# expansion_module_USB_host.net
KiCad netlist of a schematic drawn in EAGLE
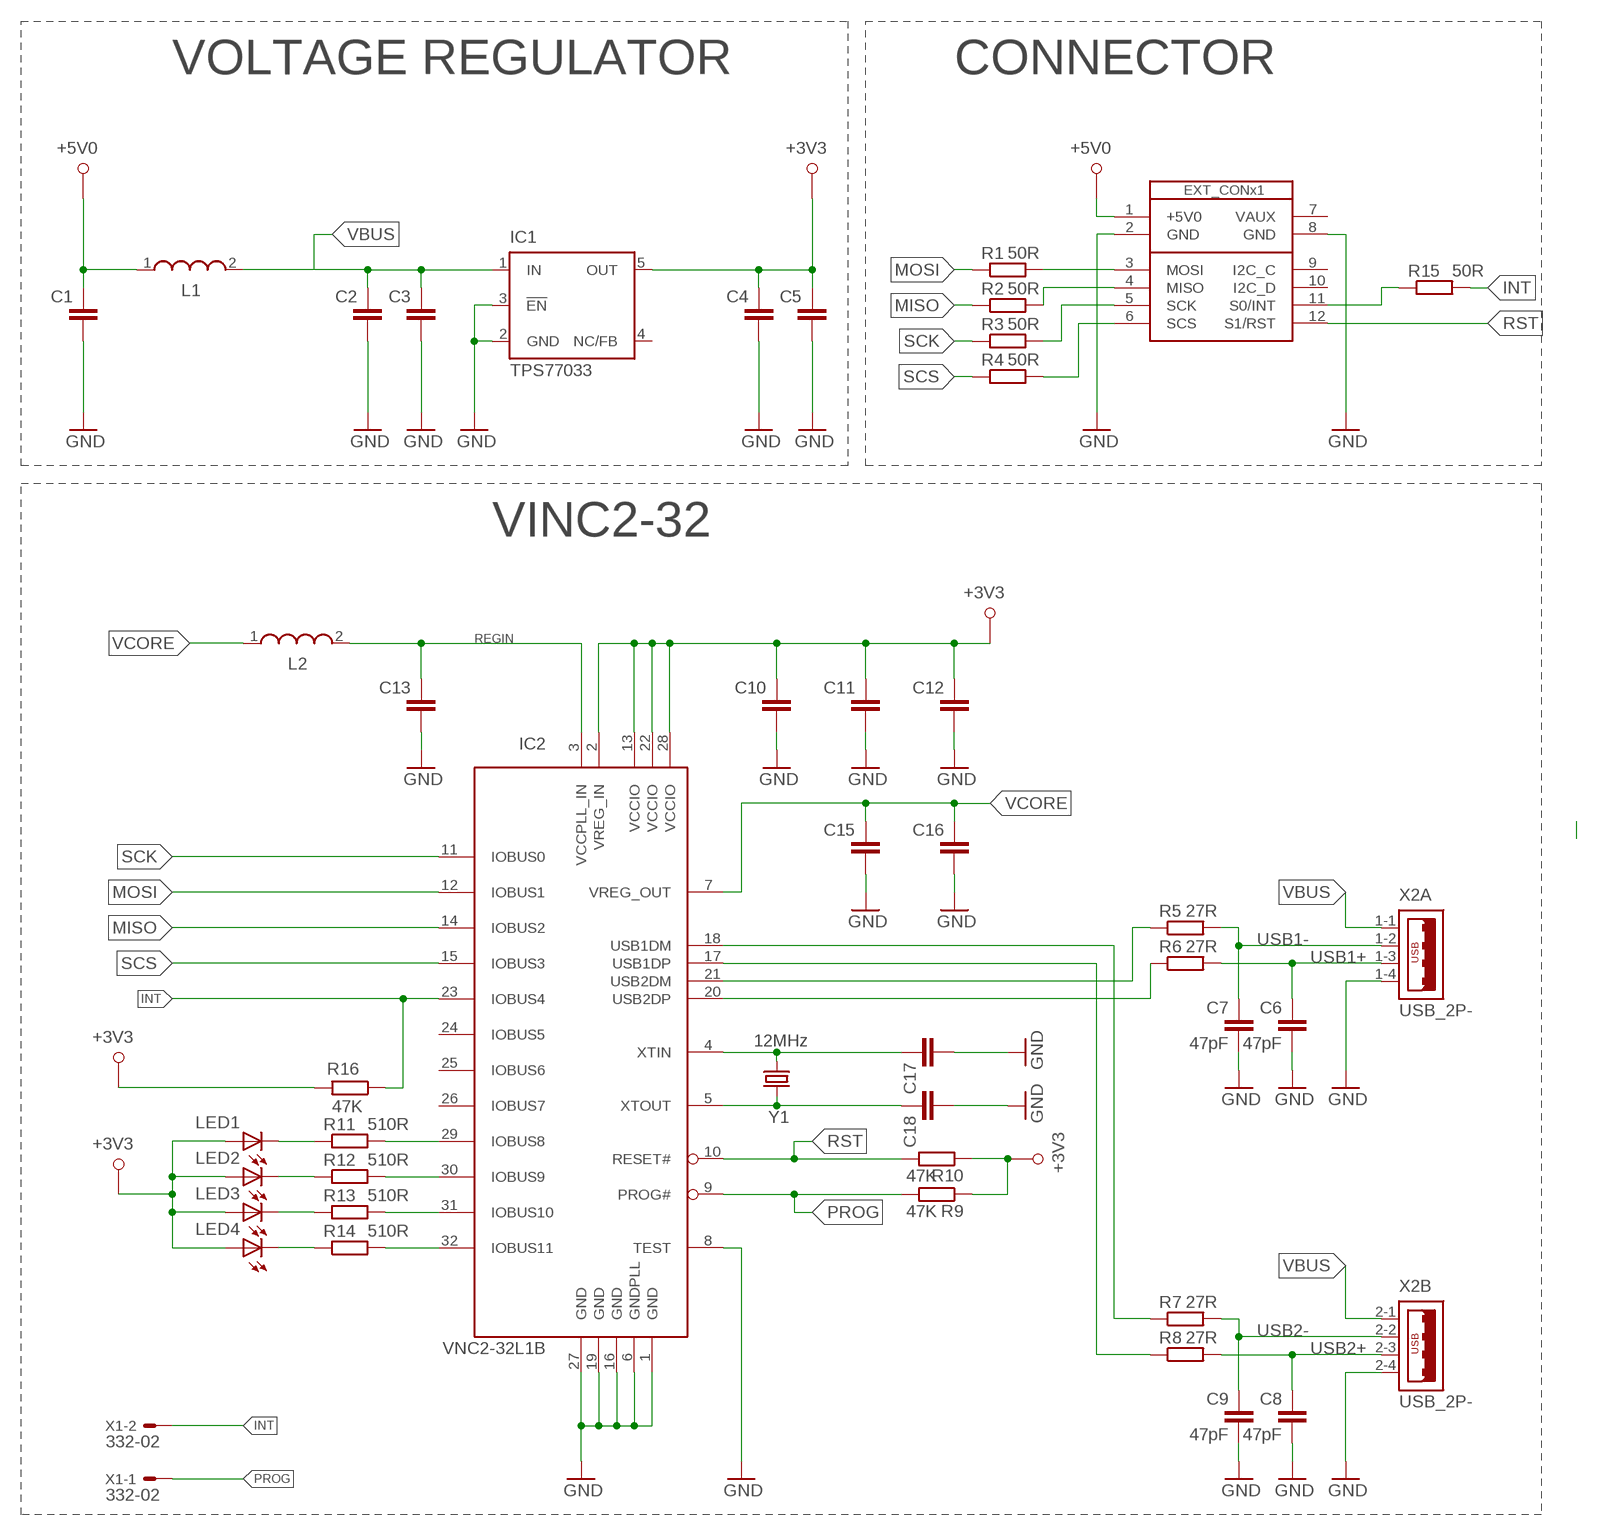
[diagram p0: schematic, sheet 1]

(export (version "E")
  (design (tool "Eeschema 10.0.6"))
  (components
    (comp (ref "C1")
      (value "C-EUC0805")
      (footprint "eagle-import:C0805")
      (libsource (lib "eagle-import") (part "C-EUC0805"))
    )
    (comp (ref "C2")
      (value "C-EUC0805")
      (footprint "eagle-import:C0805")
      (libsource (lib "eagle-import") (part "C-EUC0805"))
    )
    (comp (ref "C3")
      (value "C-EUC0805")
      (footprint "eagle-import:C0805")
      (libsource (lib "eagle-import") (part "C-EUC0805"))
    )
    (comp (ref "C4")
      (value "C-EUC0805")
      (footprint "eagle-import:C0805")
      (libsource (lib "eagle-import") (part "C-EUC0805"))
    )
    (comp (ref "C5")
      (value "C-EUC0805")
      (footprint "eagle-import:C0805")
      (libsource (lib "eagle-import") (part "C-EUC0805"))
    )
    (comp (ref "C6")
      (value "47pF")
      (footprint "eagle-import:C0805")
      (libsource (lib "eagle-import") (part "C-EUC0805"))
    )
    (comp (ref "C7")
      (value "47pF")
      (footprint "eagle-import:C0805")
      (libsource (lib "eagle-import") (part "C-EUC0805"))
    )
    (comp (ref "C8")
      (value "47pF")
      (footprint "eagle-import:C0805")
      (libsource (lib "eagle-import") (part "C-EUC0805"))
    )
    (comp (ref "C9")
      (value "47pF")
      (footprint "eagle-import:C0805")
      (libsource (lib "eagle-import") (part "C-EUC0805"))
    )
    (comp (ref "C10")
      (value "C-EUC0805")
      (footprint "eagle-import:C0805")
      (libsource (lib "eagle-import") (part "C-EUC0805"))
    )
    (comp (ref "C11")
      (value "C-EUC0805")
      (footprint "eagle-import:C0805")
      (libsource (lib "eagle-import") (part "C-EUC0805"))
    )
    (comp (ref "C12")
      (value "C-EUC0805")
      (footprint "eagle-import:C0805")
      (libsource (lib "eagle-import") (part "C-EUC0805"))
    )
    (comp (ref "C13")
      (value "C-EUC0805")
      (footprint "eagle-import:C0805")
      (libsource (lib "eagle-import") (part "C-EUC0805"))
    )
    (comp (ref "C15")
      (value "C-EUC0805")
      (footprint "eagle-import:C0805")
      (libsource (lib "eagle-import") (part "C-EUC0805"))
    )
    (comp (ref "C16")
      (value "C-EUC0805")
      (footprint "eagle-import:C0805")
      (libsource (lib "eagle-import") (part "C-EUC0805"))
    )
    (comp (ref "C17")
      (value "C-EUC0805")
      (footprint "eagle-import:C0805")
      (libsource (lib "eagle-import") (part "C-EUC0805"))
    )
    (comp (ref "C18")
      (value "C-EUC0805")
      (footprint "eagle-import:C0805")
      (libsource (lib "eagle-import") (part "C-EUC0805"))
    )
    (comp (ref "IC1")
      (value "TPS77033")
      (footprint "eagle-import:SOT23-DBV")
      (fields (field (name "MF") "TEXAS INSTRUMENTS") (field (name "MPN") "TPS77033DBVT"))
      (libsource (lib "eagle-import") (part "TPS77033"))
    )
    (comp (ref "IC2")
      (value "VNC2-32L1B")
      (footprint "eagle-import:LQFP32")
      (libsource (lib "eagle-import") (part "VNC2-32L1B"))
    )
    (comp (ref "L1")
      (value "WE-LQ_1210")
      (footprint "eagle-import:WE-LQ_M")
      (libsource (lib "eagle-import") (part "WE-LQ_1210"))
    )
    (comp (ref "L2")
      (value "WE-LQ_1210")
      (footprint "eagle-import:WE-LQ_M")
      (libsource (lib "eagle-import") (part "WE-LQ_1210"))
    )
    (comp (ref "LED1")
      (value "LEDCHIPLED_0805")
      (footprint "eagle-import:CHIPLED_0805")
      (libsource (lib "eagle-import") (part "LEDCHIPLED_0805"))
    )
    (comp (ref "LED2")
      (value "LEDCHIPLED_0805")
      (footprint "eagle-import:CHIPLED_0805")
      (libsource (lib "eagle-import") (part "LEDCHIPLED_0805"))
    )
    (comp (ref "LED3")
      (value "LEDCHIPLED_0805")
      (footprint "eagle-import:CHIPLED_0805")
      (libsource (lib "eagle-import") (part "LEDCHIPLED_0805"))
    )
    (comp (ref "LED4")
      (value "LEDCHIPLED_0805")
      (footprint "eagle-import:CHIPLED_0805")
      (libsource (lib "eagle-import") (part "LEDCHIPLED_0805"))
    )
    (comp (ref "R1")
      (value "50R")
      (footprint "eagle-import:R0805")
      (libsource (lib "eagle-import") (part "R-EU_R0805"))
    )
    (comp (ref "R2")
      (value "50R")
      (footprint "eagle-import:R0805")
      (libsource (lib "eagle-import") (part "R-EU_R0805"))
    )
    (comp (ref "R3")
      (value "50R")
      (footprint "eagle-import:R0805")
      (libsource (lib "eagle-import") (part "R-EU_R0805"))
    )
    (comp (ref "R4")
      (value "50R")
      (footprint "eagle-import:R0805")
      (libsource (lib "eagle-import") (part "R-EU_R0805"))
    )
    (comp (ref "R5")
      (value "27R")
      (footprint "eagle-import:R0805")
      (libsource (lib "eagle-import") (part "R-EU_R0805"))
    )
    (comp (ref "R6")
      (value "27R")
      (footprint "eagle-import:R0805")
      (libsource (lib "eagle-import") (part "R-EU_R0805"))
    )
    (comp (ref "R7")
      (value "27R")
      (footprint "eagle-import:R0805")
      (libsource (lib "eagle-import") (part "R-EU_R0805"))
    )
    (comp (ref "R8")
      (value "27R")
      (footprint "eagle-import:R0805")
      (libsource (lib "eagle-import") (part "R-EU_R0805"))
    )
    (comp (ref "R9")
      (value "47K")
      (footprint "eagle-import:R0805")
      (libsource (lib "eagle-import") (part "R-EU_R0805"))
    )
    (comp (ref "R10")
      (value "47K")
      (footprint "eagle-import:R0805")
      (libsource (lib "eagle-import") (part "R-EU_R0805"))
    )
    (comp (ref "R11")
      (value "510R")
      (footprint "eagle-import:R0805")
      (libsource (lib "eagle-import") (part "R-EU_R0805"))
    )
    (comp (ref "R12")
      (value "510R")
      (footprint "eagle-import:R0805")
      (libsource (lib "eagle-import") (part "R-EU_R0805"))
    )
    (comp (ref "R13")
      (value "510R")
      (footprint "eagle-import:R0805")
      (libsource (lib "eagle-import") (part "R-EU_R0805"))
    )
    (comp (ref "R14")
      (value "510R")
      (footprint "eagle-import:R0805")
      (libsource (lib "eagle-import") (part "R-EU_R0805"))
    )
    (comp (ref "R15")
      (value "50R")
      (footprint "eagle-import:R0805")
      (libsource (lib "eagle-import") (part "R-EU_R0805"))
    )
    (comp (ref "R16")
      (value "47K")
      (footprint "eagle-import:R0805")
      (libsource (lib "eagle-import") (part "R-EU_R0805"))
    )
    (comp (ref "U$1")
      (value "SB_EXT_CON_X1_SPI")
      (footprint "eagle-import:SB_EXT_CON_X1_FULL")
      (libsource (lib "eagle-import") (part "SB_EXT_CON_X1_SPI"))
    )
    (comp (ref "X1")
      (value "332-02")
      (footprint "eagle-import:332-02")
      (libsource (lib "eagle-import") (part "332-02"))
    )
    (comp (ref "X2")
      (value "USB_2P-")
      (footprint "eagle-import:85-32003-00X-1_DUAL")
      (libsource (lib "eagle-import") (part "USB_2P-"))
    )
    (comp (ref "Y1")
      (value "12MHz")
      (footprint "eagle-import:CRYSTAL-SMD-5X3")
      (libsource (lib "eagle-import") (part "CRYSTALCRYSTAL-SMD-5X3-12MHZ"))
    )
  )
  (nets
    (net (code "1") (name "+3V3") (class "Default")
      (node (ref "C10") (pin "2") (pinfunction "2_2") (pintype "passive"))
      (node (ref "C11") (pin "2") (pinfunction "2_2") (pintype "passive"))
      (node (ref "C12") (pin "2") (pinfunction "2_2") (pintype "passive"))
      (node (ref "C4") (pin "2") (pinfunction "2_2") (pintype "passive"))
      (node (ref "C5") (pin "2") (pinfunction "2_2") (pintype "passive"))
      (node (ref "IC1") (pin "5") (pinfunction "OUT_5") (pintype "passive"))
      (node (ref "IC2") (pin "13") (pinfunction "VCCIO_13") (pintype "power_in"))
      (node (ref "IC2") (pin "2") (pinfunction "VREG_IN_2") (pintype "power_in"))
      (node (ref "IC2") (pin "22") (pinfunction "VCCIO_22") (pintype "power_in"))
      (node (ref "IC2") (pin "28") (pinfunction "VCCIO_28") (pintype "power_in"))
      (node (ref "LED1") (pin "A") (pinfunction "A_A") (pintype "passive"))
      (node (ref "LED2") (pin "A") (pinfunction "A_A") (pintype "passive"))
      (node (ref "LED3") (pin "A") (pinfunction "A_A") (pintype "passive"))
      (node (ref "LED4") (pin "A") (pinfunction "A_A") (pintype "passive"))
      (node (ref "R10") (pin "1") (pinfunction "1_1") (pintype "passive"))
      (node (ref "R16") (pin "2") (pinfunction "2_2") (pintype "passive"))
      (node (ref "R9") (pin "1") (pinfunction "1_1") (pintype "passive"))
    )
    (net (code "2") (name "+5V0") (class "Default")
      (node (ref "C1") (pin "2") (pinfunction "2_2") (pintype "passive"))
      (node (ref "L1") (pin "1") (pinfunction "1_1") (pintype "passive"))
      (node (ref "U$1") (pin "1") (pinfunction "+5V0_1") (pintype "bidirectional"))
    )
    (net (code "3") (name "/REGIN") (class "Default")
      (node (ref "C13") (pin "2") (pinfunction "2_2") (pintype "passive"))
      (node (ref "IC2") (pin "3") (pinfunction "VCCPLL_IN_3") (pintype "power_in"))
      (node (ref "L2") (pin "2") (pinfunction "2_2") (pintype "passive"))
    )
    (net (code "4") (name "/USB1+") (class "Default")
      (node (ref "C6") (pin "2") (pinfunction "2_2") (pintype "passive"))
      (node (ref "R6") (pin "2") (pinfunction "2_2") (pintype "passive"))
      (node (ref "X2") (pin "1-3") (pinfunction "3_1-3") (pintype "passive"))
    )
    (net (code "5") (name "/USB1-") (class "Default")
      (node (ref "C7") (pin "2") (pinfunction "2_2") (pintype "passive"))
      (node (ref "R5") (pin "2") (pinfunction "2_2") (pintype "passive"))
      (node (ref "X2") (pin "1-2") (pinfunction "2_1-2") (pintype "passive"))
    )
    (net (code "6") (name "/USB2+") (class "Default")
      (node (ref "C8") (pin "2") (pinfunction "2_2") (pintype "passive"))
      (node (ref "R8") (pin "2") (pinfunction "2_2") (pintype "passive"))
      (node (ref "X2") (pin "2-3") (pinfunction "3_2-3") (pintype "passive"))
    )
    (net (code "7") (name "/USB2-") (class "Default")
      (node (ref "C9") (pin "2") (pinfunction "2_2") (pintype "passive"))
      (node (ref "R7") (pin "2") (pinfunction "2_2") (pintype "passive"))
      (node (ref "X2") (pin "2-2") (pinfunction "2_2-2") (pintype "passive"))
    )
    (net (code "8") (name "GND") (class "Default")
      (node (ref "C1") (pin "1") (pinfunction "1_1") (pintype "passive"))
      (node (ref "C10") (pin "1") (pinfunction "1_1") (pintype "passive"))
      (node (ref "C11") (pin "1") (pinfunction "1_1") (pintype "passive"))
      (node (ref "C12") (pin "1") (pinfunction "1_1") (pintype "passive"))
      (node (ref "C13") (pin "1") (pinfunction "1_1") (pintype "passive"))
      (node (ref "C15") (pin "1") (pinfunction "1_1") (pintype "passive"))
      (node (ref "C16") (pin "1") (pinfunction "1_1") (pintype "passive"))
      (node (ref "C17") (pin "1") (pinfunction "1_1") (pintype "passive"))
      (node (ref "C18") (pin "1") (pinfunction "1_1") (pintype "passive"))
      (node (ref "C2") (pin "1") (pinfunction "1_1") (pintype "passive"))
      (node (ref "C3") (pin "1") (pinfunction "1_1") (pintype "passive"))
      (node (ref "C4") (pin "1") (pinfunction "1_1") (pintype "passive"))
      (node (ref "C5") (pin "1") (pinfunction "1_1") (pintype "passive"))
      (node (ref "C6") (pin "1") (pinfunction "1_1") (pintype "passive"))
      (node (ref "C7") (pin "1") (pinfunction "1_1") (pintype "passive"))
      (node (ref "C8") (pin "1") (pinfunction "1_1") (pintype "passive"))
      (node (ref "C9") (pin "1") (pinfunction "1_1") (pintype "passive"))
      (node (ref "IC1") (pin "2") (pinfunction "GND_2") (pintype "power_in"))
      (node (ref "IC1") (pin "3") (pinfunction "~{EN}_3") (pintype "input"))
      (node (ref "IC2") (pin "1") (pinfunction "GND_1") (pintype "power_in"))
      (node (ref "IC2") (pin "16") (pinfunction "GND_16") (pintype "power_in"))
      (node (ref "IC2") (pin "19") (pinfunction "GND_19") (pintype "power_in"))
      (node (ref "IC2") (pin "27") (pinfunction "GND_27") (pintype "power_in"))
      (node (ref "IC2") (pin "6") (pinfunction "GNDPLL_6") (pintype "power_in"))
      (node (ref "IC2") (pin "8") (pinfunction "TEST_8") (pintype "input"))
      (node (ref "U$1") (pin "2") (pinfunction "GND_2") (pintype "bidirectional"))
      (node (ref "U$1") (pin "8") (pinfunction "GND_8") (pintype "bidirectional"))
      (node (ref "X2") (pin "1-4") (pinfunction "4_1-4") (pintype "passive"))
      (node (ref "X2") (pin "2-4") (pinfunction "4_2-4") (pintype "passive"))
    )
    (net (code "9") (name "INT") (class "Default")
      (node (ref "IC2") (pin "23") (pinfunction "IOBUS4_23") (pintype "bidirectional"))
      (node (ref "R15") (pin "2") (pinfunction "2_2") (pintype "passive"))
      (node (ref "R16") (pin "1") (pinfunction "1_1") (pintype "passive"))
      (node (ref "X1") (pin "2") (pinfunction "S_2") (pintype "passive"))
    )
    (net (code "10") (name "MISO") (class "Default")
      (node (ref "IC2") (pin "14") (pinfunction "IOBUS2_14") (pintype "bidirectional"))
      (node (ref "R2") (pin "1") (pinfunction "1_1") (pintype "passive"))
    )
    (net (code "11") (name "MOSI") (class "Default")
      (node (ref "IC2") (pin "12") (pinfunction "IOBUS1_12") (pintype "bidirectional"))
      (node (ref "R1") (pin "1") (pinfunction "1_1") (pintype "passive"))
    )
    (net (code "12") (name "Net-(IC2-IOBUS8)") (class "Default")
      (node (ref "IC2") (pin "29") (pinfunction "IOBUS8_29") (pintype "bidirectional"))
      (node (ref "R11") (pin "2") (pinfunction "2_2") (pintype "passive"))
    )
    (net (code "13") (name "Net-(IC2-IOBUS9)") (class "Default")
      (node (ref "IC2") (pin "30") (pinfunction "IOBUS9_30") (pintype "bidirectional"))
      (node (ref "R12") (pin "2") (pinfunction "2_2") (pintype "passive"))
    )
    (net (code "14") (name "Net-(IC2-IOBUS10)") (class "Default")
      (node (ref "IC2") (pin "31") (pinfunction "IOBUS10_31") (pintype "bidirectional"))
      (node (ref "R13") (pin "2") (pinfunction "2_2") (pintype "passive"))
    )
    (net (code "15") (name "Net-(IC2-IOBUS11)") (class "Default")
      (node (ref "IC2") (pin "32") (pinfunction "IOBUS11_32") (pintype "bidirectional"))
      (node (ref "R14") (pin "2") (pinfunction "2_2") (pintype "passive"))
    )
    (net (code "16") (name "Net-(IC2-USB1DM)") (class "Default")
      (node (ref "IC2") (pin "18") (pinfunction "USB1DM_18") (pintype "bidirectional"))
      (node (ref "R7") (pin "1") (pinfunction "1_1") (pintype "passive"))
    )
    (net (code "17") (name "Net-(IC2-USB1DP)") (class "Default")
      (node (ref "IC2") (pin "17") (pinfunction "USB1DP_17") (pintype "bidirectional"))
      (node (ref "R8") (pin "1") (pinfunction "1_1") (pintype "passive"))
    )
    (net (code "18") (name "Net-(IC2-USB2DM)") (class "Default")
      (node (ref "IC2") (pin "21") (pinfunction "USB2DM_21") (pintype "bidirectional"))
      (node (ref "R5") (pin "1") (pinfunction "1_1") (pintype "passive"))
    )
    (net (code "19") (name "Net-(IC2-USB2DP)") (class "Default")
      (node (ref "IC2") (pin "20") (pinfunction "USB2DP_20") (pintype "bidirectional"))
      (node (ref "R6") (pin "1") (pinfunction "1_1") (pintype "passive"))
    )
    (net (code "20") (name "Net-(IC2-XTIN)") (class "Default")
      (node (ref "C17") (pin "2") (pinfunction "2_2") (pintype "passive"))
      (node (ref "IC2") (pin "4") (pinfunction "XTIN_4") (pintype "input"))
      (node (ref "Y1") (pin "1") (pinfunction "1_1") (pintype "passive"))
    )
    (net (code "21") (name "Net-(IC2-XTOUT)") (class "Default")
      (node (ref "C18") (pin "2") (pinfunction "2_2") (pintype "passive"))
      (node (ref "IC2") (pin "5") (pinfunction "XTOUT_5") (pintype "output"))
      (node (ref "Y1") (pin "3") (pinfunction "2_3") (pintype "passive"))
    )
    (net (code "22") (name "Net-(LED1-PadC)") (class "Default")
      (node (ref "LED1") (pin "C") (pinfunction "C_C") (pintype "passive"))
      (node (ref "R11") (pin "1") (pinfunction "1_1") (pintype "passive"))
    )
    (net (code "23") (name "Net-(LED2-PadC)") (class "Default")
      (node (ref "LED2") (pin "C") (pinfunction "C_C") (pintype "passive"))
      (node (ref "R12") (pin "1") (pinfunction "1_1") (pintype "passive"))
    )
    (net (code "24") (name "Net-(LED3-PadC)") (class "Default")
      (node (ref "LED3") (pin "C") (pinfunction "C_C") (pintype "passive"))
      (node (ref "R13") (pin "1") (pinfunction "1_1") (pintype "passive"))
    )
    (net (code "25") (name "Net-(LED4-PadC)") (class "Default")
      (node (ref "LED4") (pin "C") (pinfunction "C_C") (pintype "passive"))
      (node (ref "R14") (pin "1") (pinfunction "1_1") (pintype "passive"))
    )
    (net (code "26") (name "Net-(U$1-MISO)") (class "Default")
      (node (ref "R2") (pin "2") (pinfunction "2_2") (pintype "passive"))
      (node (ref "U$1") (pin "4") (pinfunction "MISO_4") (pintype "bidirectional"))
    )
    (net (code "27") (name "Net-(U$1-MOSI)") (class "Default")
      (node (ref "R1") (pin "2") (pinfunction "2_2") (pintype "passive"))
      (node (ref "U$1") (pin "3") (pinfunction "MOSI_3") (pintype "bidirectional"))
    )
    (net (code "28") (name "Net-(U$1-S0{slash}INT)") (class "Default")
      (node (ref "R15") (pin "1") (pinfunction "1_1") (pintype "passive"))
      (node (ref "U$1") (pin "11") (pinfunction "S0/INT_11") (pintype "bidirectional"))
    )
    (net (code "29") (name "Net-(U$1-SCK)") (class "Default")
      (node (ref "R3") (pin "2") (pinfunction "2_2") (pintype "passive"))
      (node (ref "U$1") (pin "5") (pinfunction "SCK_5") (pintype "bidirectional"))
    )
    (net (code "30") (name "Net-(U$1-SCS)") (class "Default")
      (node (ref "R4") (pin "2") (pinfunction "2_2") (pintype "passive"))
      (node (ref "U$1") (pin "6") (pinfunction "SCS_6") (pintype "bidirectional"))
    )
    (net (code "31") (name "PROG") (class "Default")
      (node (ref "IC2") (pin "9") (pinfunction "PROG#_9") (pintype "input"))
      (node (ref "R9") (pin "2") (pinfunction "2_2") (pintype "passive"))
      (node (ref "X1") (pin "1") (pinfunction "S_1") (pintype "passive"))
    )
    (net (code "32") (name "RST") (class "Default")
      (node (ref "IC2") (pin "10") (pinfunction "RESET#_10") (pintype "input"))
      (node (ref "R10") (pin "2") (pinfunction "2_2") (pintype "passive"))
      (node (ref "U$1") (pin "12") (pinfunction "S1/RST_12") (pintype "bidirectional"))
    )
    (net (code "33") (name "SCK") (class "Default")
      (node (ref "IC2") (pin "11") (pinfunction "IOBUS0_11") (pintype "bidirectional"))
      (node (ref "R3") (pin "1") (pinfunction "1_1") (pintype "passive"))
    )
    (net (code "34") (name "SCS") (class "Default")
      (node (ref "IC2") (pin "15") (pinfunction "IOBUS3_15") (pintype "bidirectional"))
      (node (ref "R4") (pin "1") (pinfunction "1_1") (pintype "passive"))
    )
    (net (code "35") (name "VBUS") (class "Default")
      (node (ref "C2") (pin "2") (pinfunction "2_2") (pintype "passive"))
      (node (ref "C3") (pin "2") (pinfunction "2_2") (pintype "passive"))
      (node (ref "IC1") (pin "1") (pinfunction "IN_1") (pintype "input"))
      (node (ref "L1") (pin "2") (pinfunction "2_2") (pintype "passive"))
      (node (ref "X2") (pin "1-1") (pinfunction "1_1-1") (pintype "passive"))
      (node (ref "X2") (pin "2-1") (pinfunction "1_2-1") (pintype "passive"))
    )
    (net (code "36") (name "VCORE") (class "Default")
      (node (ref "C15") (pin "2") (pinfunction "2_2") (pintype "passive"))
      (node (ref "C16") (pin "2") (pinfunction "2_2") (pintype "passive"))
      (node (ref "IC2") (pin "7") (pinfunction "VREG_OUT_7") (pintype "output"))
      (node (ref "L2") (pin "1") (pinfunction "1_1") (pintype "passive"))
    )
    (net (code "37") (name "unconnected-(IC1-NC{slash}FB-Pad4)") (class "Default")
      (node (ref "IC1") (pin "4") (pinfunction "NC/FB_4") (pintype "passive"))
    )
    (net (code "38") (name "unconnected-(IC2-IOBUS5-Pad24)") (class "Default")
      (node (ref "IC2") (pin "24") (pinfunction "IOBUS5_24") (pintype "bidirectional"))
    )
    (net (code "39") (name "unconnected-(IC2-IOBUS6-Pad25)") (class "Default")
      (node (ref "IC2") (pin "25") (pinfunction "IOBUS6_25") (pintype "bidirectional"))
    )
    (net (code "40") (name "unconnected-(IC2-IOBUS7-Pad26)") (class "Default")
      (node (ref "IC2") (pin "26") (pinfunction "IOBUS7_26") (pintype "bidirectional"))
    )
    (net (code "41") (name "unconnected-(U$1-I2C_C-Pad9)") (class "Default")
      (node (ref "U$1") (pin "9") (pinfunction "I2C_C_9") (pintype "bidirectional"))
    )
    (net (code "42") (name "unconnected-(U$1-I2C_D-Pad10)") (class "Default")
      (node (ref "U$1") (pin "10") (pinfunction "I2C_D_10") (pintype "bidirectional"))
    )
    (net (code "43") (name "unconnected-(U$1-VAUX-Pad7)") (class "Default")
      (node (ref "U$1") (pin "7") (pinfunction "VAUX_7") (pintype "bidirectional"))
    )
  )
)
